# 02_Solenoid_Driver.net
KiCad netlist of a schematic drawn in Altium Designer
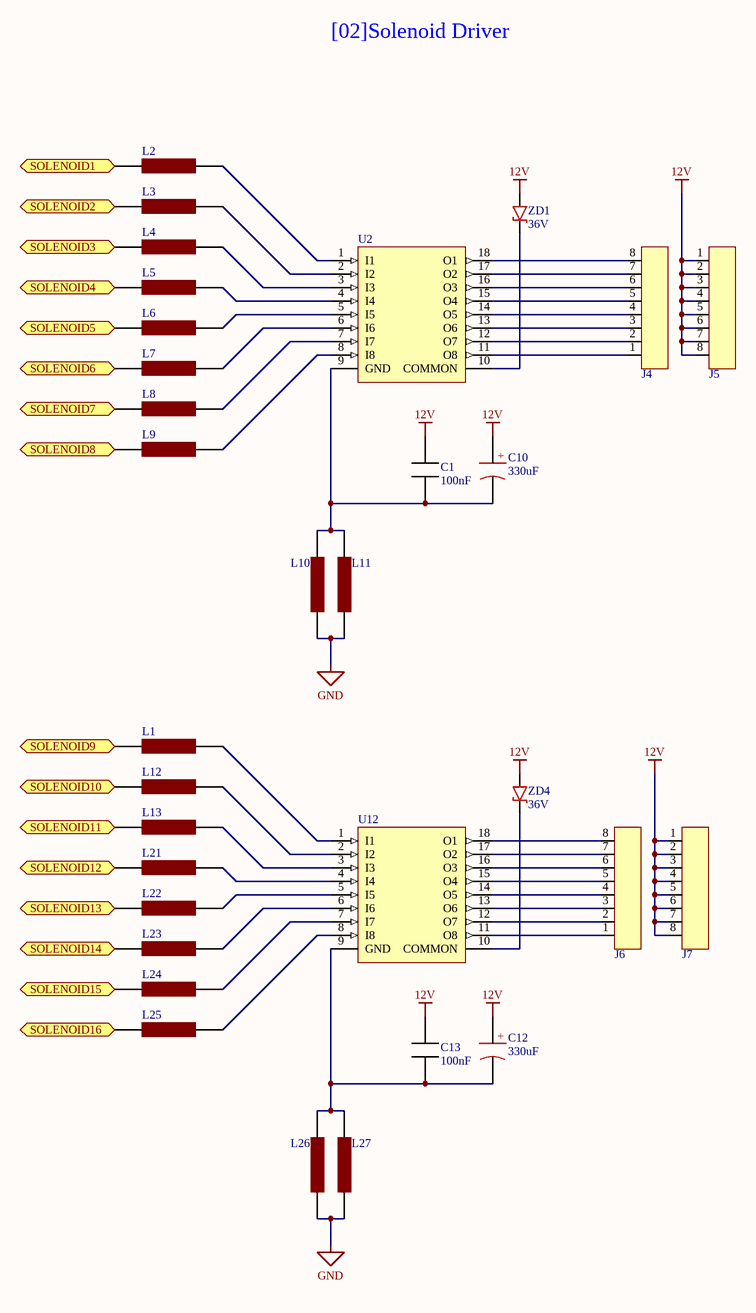
[diagram p0: [02]Solenoid Driver.SchDoc]

(export (version "E")
  (design (tool "Eeschema 10.0.6"))
  (components
    (comp (ref "C1")
      (value "100nF")
      (footprint "CAPC2012X09N")
      (description "CAP CER 0.1UF 50V Y5V 0805")
      (fields
        (field (name "MANUFACTURER") "Samsung Electro-Mechanics America, Inc.")
        (field (name "MANUFACTURER PART NUMBER") "CL21F104ZBCNNNC")
      )
      (libsource (lib "AMMDK Parts") (part "CL21F104ZBCNNNC"))
    )
    (comp (ref "C10")
      (value "330uF")
      (footprint "CAPAE137130X140M")
      (description "CAP ALUM 330UF 20% 35V SMD")
      (libsource (lib "AMMDK Parts") (part "EMVH350ARA331MKE0S"))
    )
    (comp (ref "C12")
      (value "330uF")
      (footprint "CAPAE137130X140M")
      (description "CAP ALUM 330UF 20% 35V SMD")
      (libsource (lib "AMMDK Parts") (part "EMVH350ARA331MKE0S"))
    )
    (comp (ref "C13")
      (value "100nF")
      (footprint "CAPC2012X09N")
      (description "CAP CER 0.1UF 50V Y5V 0805")
      (fields
        (field (name "MANUFACTURER") "Samsung Electro-Mechanics America, Inc.")
        (field (name "MANUFACTURER PART NUMBER") "CL21F104ZBCNNNC")
      )
      (libsource (lib "AMMDK Parts") (part "CL21F104ZBCNNNC"))
    )
    (comp (ref "J4")
      (value "1771156")
      (footprint "1771156")
      (description "CONN TERM BLK 8POS 2.5MM SMD")
      (fields (field (name "MANUFACTURER") "Phoenix Contact"))
      (libsource (lib "") (part "1771156_1"))
    )
    (comp (ref "J5")
      (value "1771156")
      (footprint "1771156")
      (description "CONN TERM BLK 8POS 2.5MM SMD")
      (fields (field (name "MANUFACTURER") "Phoenix Contact"))
      (libsource (lib "AMMDK Parts") (part "1771156"))
    )
    (comp (ref "J6")
      (value "1771156")
      (footprint "1771156")
      (description "CONN TERM BLK 8POS 2.5MM SMD")
      (fields (field (name "MANUFACTURER") "Phoenix Contact"))
      (libsource (lib "") (part "1771156_1"))
    )
    (comp (ref "J7")
      (value "1771156")
      (footprint "1771156")
      (description "CONN TERM BLK 8POS 2.5MM SMD")
      (fields (field (name "MANUFACTURER") "Phoenix Contact"))
      (libsource (lib "AMMDK Parts") (part "1771156"))
    )
    (comp (ref "L1")
      (value "MH2029-300Y")
      (footprint "INDC2012X11N")
      (description "EMI Filter Beads, Chips & Arrays Impedance 30ohms IDC 3.0")
      (fields (field (name "MANUFACTURER") "Bourns") (field (name "TOLERANCE") "25 %"))
      (libsource (lib "AMMDK Parts") (part "MH2029-300Y"))
    )
    (comp (ref "L2")
      (value "MH2029-300Y")
      (footprint "INDC2012X11N")
      (description "EMI Filter Beads, Chips & Arrays Impedance 30ohms IDC 3.0")
      (fields (field (name "MANUFACTURER") "Bourns") (field (name "TOLERANCE") "25 %"))
      (libsource (lib "AMMDK Parts") (part "MH2029-300Y"))
    )
    (comp (ref "L3")
      (value "MH2029-300Y")
      (footprint "INDC2012X11N")
      (description "EMI Filter Beads, Chips & Arrays Impedance 30ohms IDC 3.0")
      (fields (field (name "MANUFACTURER") "Bourns") (field (name "TOLERANCE") "25 %"))
      (libsource (lib "AMMDK Parts") (part "MH2029-300Y"))
    )
    (comp (ref "L4")
      (value "MH2029-300Y")
      (footprint "INDC2012X11N")
      (description "EMI Filter Beads, Chips & Arrays Impedance 30ohms IDC 3.0")
      (fields (field (name "MANUFACTURER") "Bourns") (field (name "TOLERANCE") "25 %"))
      (libsource (lib "AMMDK Parts") (part "MH2029-300Y"))
    )
    (comp (ref "L5")
      (value "MH2029-300Y")
      (footprint "INDC2012X11N")
      (description "EMI Filter Beads, Chips & Arrays Impedance 30ohms IDC 3.0")
      (fields (field (name "MANUFACTURER") "Bourns") (field (name "TOLERANCE") "25 %"))
      (libsource (lib "AMMDK Parts") (part "MH2029-300Y"))
    )
    (comp (ref "L6")
      (value "MH2029-300Y")
      (footprint "INDC2012X11N")
      (description "EMI Filter Beads, Chips & Arrays Impedance 30ohms IDC 3.0")
      (fields (field (name "MANUFACTURER") "Bourns") (field (name "TOLERANCE") "25 %"))
      (libsource (lib "AMMDK Parts") (part "MH2029-300Y"))
    )
    (comp (ref "L7")
      (value "MH2029-300Y")
      (footprint "INDC2012X11N")
      (description "EMI Filter Beads, Chips & Arrays Impedance 30ohms IDC 3.0")
      (fields (field (name "MANUFACTURER") "Bourns") (field (name "TOLERANCE") "25 %"))
      (libsource (lib "AMMDK Parts") (part "MH2029-300Y"))
    )
    (comp (ref "L8")
      (value "MH2029-300Y")
      (footprint "INDC2012X11N")
      (description "EMI Filter Beads, Chips & Arrays Impedance 30ohms IDC 3.0")
      (fields (field (name "MANUFACTURER") "Bourns") (field (name "TOLERANCE") "25 %"))
      (libsource (lib "AMMDK Parts") (part "MH2029-300Y"))
    )
    (comp (ref "L9")
      (value "MH2029-300Y")
      (footprint "INDC2012X11N")
      (description "EMI Filter Beads, Chips & Arrays Impedance 30ohms IDC 3.0")
      (fields (field (name "MANUFACTURER") "Bourns") (field (name "TOLERANCE") "25 %"))
      (libsource (lib "AMMDK Parts") (part "MH2029-300Y"))
    )
    (comp (ref "L10")
      (value "MH2029-300Y")
      (footprint "INDC2012X11N")
      (description "EMI Filter Beads, Chips & Arrays Impedance 30ohms IDC 3.0")
      (fields (field (name "MANUFACTURER") "Bourns") (field (name "TOLERANCE") "25 %"))
      (libsource (lib "") (part "MH2029-300Y_1"))
    )
    (comp (ref "L11")
      (value "MH2029-300Y")
      (footprint "INDC2012X11N")
      (description "EMI Filter Beads, Chips & Arrays Impedance 30ohms IDC 3.0")
      (fields (field (name "MANUFACTURER") "Bourns") (field (name "TOLERANCE") "25 %"))
      (libsource (lib "") (part "MH2029-300Y_1"))
    )
    (comp (ref "L12")
      (value "MH2029-300Y")
      (footprint "INDC2012X11N")
      (description "EMI Filter Beads, Chips & Arrays Impedance 30ohms IDC 3.0")
      (fields (field (name "MANUFACTURER") "Bourns") (field (name "TOLERANCE") "25 %"))
      (libsource (lib "AMMDK Parts") (part "MH2029-300Y"))
    )
    (comp (ref "L13")
      (value "MH2029-300Y")
      (footprint "INDC2012X11N")
      (description "EMI Filter Beads, Chips & Arrays Impedance 30ohms IDC 3.0")
      (fields (field (name "MANUFACTURER") "Bourns") (field (name "TOLERANCE") "25 %"))
      (libsource (lib "AMMDK Parts") (part "MH2029-300Y"))
    )
    (comp (ref "L21")
      (value "MH2029-300Y")
      (footprint "INDC2012X11N")
      (description "EMI Filter Beads, Chips & Arrays Impedance 30ohms IDC 3.0")
      (fields (field (name "MANUFACTURER") "Bourns") (field (name "TOLERANCE") "25 %"))
      (libsource (lib "AMMDK Parts") (part "MH2029-300Y"))
    )
    (comp (ref "L22")
      (value "MH2029-300Y")
      (footprint "INDC2012X11N")
      (description "EMI Filter Beads, Chips & Arrays Impedance 30ohms IDC 3.0")
      (fields (field (name "MANUFACTURER") "Bourns") (field (name "TOLERANCE") "25 %"))
      (libsource (lib "AMMDK Parts") (part "MH2029-300Y"))
    )
    (comp (ref "L23")
      (value "MH2029-300Y")
      (footprint "INDC2012X11N")
      (description "EMI Filter Beads, Chips & Arrays Impedance 30ohms IDC 3.0")
      (fields (field (name "MANUFACTURER") "Bourns") (field (name "TOLERANCE") "25 %"))
      (libsource (lib "AMMDK Parts") (part "MH2029-300Y"))
    )
    (comp (ref "L24")
      (value "MH2029-300Y")
      (footprint "INDC2012X11N")
      (description "EMI Filter Beads, Chips & Arrays Impedance 30ohms IDC 3.0")
      (fields (field (name "MANUFACTURER") "Bourns") (field (name "TOLERANCE") "25 %"))
      (libsource (lib "AMMDK Parts") (part "MH2029-300Y"))
    )
    (comp (ref "L25")
      (value "MH2029-300Y")
      (footprint "INDC2012X11N")
      (description "EMI Filter Beads, Chips & Arrays Impedance 30ohms IDC 3.0")
      (fields (field (name "MANUFACTURER") "Bourns") (field (name "TOLERANCE") "25 %"))
      (libsource (lib "AMMDK Parts") (part "MH2029-300Y"))
    )
    (comp (ref "L26")
      (value "MH2029-300Y")
      (footprint "INDC2012X11N")
      (description "EMI Filter Beads, Chips & Arrays Impedance 30ohms IDC 3.0")
      (fields (field (name "MANUFACTURER") "Bourns") (field (name "TOLERANCE") "25 %"))
      (libsource (lib "") (part "MH2029-300Y_1"))
    )
    (comp (ref "L27")
      (value "MH2029-300Y")
      (footprint "INDC2012X11N")
      (description "EMI Filter Beads, Chips & Arrays Impedance 30ohms IDC 3.0")
      (fields (field (name "MANUFACTURER") "Bourns") (field (name "TOLERANCE") "25 %"))
      (libsource (lib "") (part "MH2029-300Y_1"))
    )
    (comp (ref "U2")
      (value "TBD62083A")
      (footprint "TSOP65P640X155-18N")
      (description "8channel source type DMOS transistor array")
      (libsource (lib "AMMDK Parts") (part "TBD62083A"))
    )
    (comp (ref "U12")
      (value "TBD62083A")
      (footprint "TSOP65P640X155-18N")
      (description "8channel source type DMOS transistor array")
      (libsource (lib "AMMDK Parts") (part "TBD62083A"))
    )
    (comp (ref "ZD1")
      (value "36V")
      (footprint "SOT95P237X111-3N")
      (description "Zener Diode 36V 225mW ±6%")
      (libsource (lib "AMMDK Parts") (part "BZX84C36LT1G"))
    )
    (comp (ref "ZD4")
      (value "36V")
      (footprint "SOT95P237X111-3N")
      (description "Zener Diode 36V 225mW ±6%")
      (libsource (lib "AMMDK Parts") (part "BZX84C36LT1G"))
    )
  )
  (nets
    (net (code "1") (name "/SOLENOID1") (class "Default")
      (node (ref "L2") (pin "1") (pinfunction "1_1") (pintype "passive"))
    )
    (net (code "2") (name "/SOLENOID2") (class "Default")
      (node (ref "L3") (pin "1") (pinfunction "1_1") (pintype "passive"))
    )
    (net (code "3") (name "/SOLENOID3") (class "Default")
      (node (ref "L4") (pin "1") (pinfunction "1_1") (pintype "passive"))
    )
    (net (code "4") (name "/SOLENOID4") (class "Default")
      (node (ref "L5") (pin "1") (pinfunction "1_1") (pintype "passive"))
    )
    (net (code "5") (name "/SOLENOID5") (class "Default")
      (node (ref "L6") (pin "1") (pinfunction "1_1") (pintype "passive"))
    )
    (net (code "6") (name "/SOLENOID6") (class "Default")
      (node (ref "L7") (pin "1") (pinfunction "1_1") (pintype "passive"))
    )
    (net (code "7") (name "/SOLENOID7") (class "Default")
      (node (ref "L8") (pin "1") (pinfunction "1_1") (pintype "passive"))
    )
    (net (code "8") (name "/SOLENOID8") (class "Default")
      (node (ref "L9") (pin "1") (pinfunction "1_1") (pintype "passive"))
    )
    (net (code "9") (name "/SOLENOID9") (class "Default")
      (node (ref "L1") (pin "1") (pinfunction "1_1") (pintype "passive"))
    )
    (net (code "10") (name "/SOLENOID10") (class "Default")
      (node (ref "L12") (pin "1") (pinfunction "1_1") (pintype "passive"))
    )
    (net (code "11") (name "/SOLENOID11") (class "Default")
      (node (ref "L13") (pin "1") (pinfunction "1_1") (pintype "passive"))
    )
    (net (code "12") (name "/SOLENOID12") (class "Default")
      (node (ref "L21") (pin "1") (pinfunction "1_1") (pintype "passive"))
    )
    (net (code "13") (name "/SOLENOID13") (class "Default")
      (node (ref "L22") (pin "1") (pinfunction "1_1") (pintype "passive"))
    )
    (net (code "14") (name "/SOLENOID14") (class "Default")
      (node (ref "L23") (pin "1") (pinfunction "1_1") (pintype "passive"))
    )
    (net (code "15") (name "/SOLENOID15") (class "Default")
      (node (ref "L24") (pin "1") (pinfunction "1_1") (pintype "passive"))
    )
    (net (code "16") (name "/SOLENOID16") (class "Default")
      (node (ref "L25") (pin "1") (pinfunction "1_1") (pintype "passive"))
    )
    (net (code "17") (name "12V") (class "Default")
      (node (ref "C1") (pin "2") (pinfunction "2_2") (pintype "passive"))
      (node (ref "C10") (pin "1") (pinfunction "1_1") (pintype "passive"))
      (node (ref "C12") (pin "1") (pinfunction "1_1") (pintype "passive"))
      (node (ref "C13") (pin "2") (pinfunction "2_2") (pintype "passive"))
      (node (ref "J5") (pin "1") (pinfunction "1_1") (pintype "passive"))
      (node (ref "J5") (pin "2") (pinfunction "2_2") (pintype "passive"))
      (node (ref "J5") (pin "3") (pinfunction "3_3") (pintype "passive"))
      (node (ref "J5") (pin "4") (pinfunction "4_4") (pintype "passive"))
      (node (ref "J5") (pin "5") (pinfunction "5_5") (pintype "passive"))
      (node (ref "J5") (pin "6") (pinfunction "6_6") (pintype "passive"))
      (node (ref "J5") (pin "7") (pinfunction "7_7") (pintype "passive"))
      (node (ref "J5") (pin "8") (pinfunction "8_8") (pintype "passive"))
      (node (ref "J7") (pin "1") (pinfunction "1_1") (pintype "passive"))
      (node (ref "J7") (pin "2") (pinfunction "2_2") (pintype "passive"))
      (node (ref "J7") (pin "3") (pinfunction "3_3") (pintype "passive"))
      (node (ref "J7") (pin "4") (pinfunction "4_4") (pintype "passive"))
      (node (ref "J7") (pin "5") (pinfunction "5_5") (pintype "passive"))
      (node (ref "J7") (pin "6") (pinfunction "6_6") (pintype "passive"))
      (node (ref "J7") (pin "7") (pinfunction "7_7") (pintype "passive"))
      (node (ref "J7") (pin "8") (pinfunction "8_8") (pintype "passive"))
      (node (ref "ZD1") (pin "A") (pinfunction "A_A") (pintype "passive"))
      (node (ref "ZD4") (pin "A") (pinfunction "A_A") (pintype "passive"))
    )
    (net (code "18") (name "GND") (class "Default")
      (node (ref "L10") (pin "1") (pinfunction "1_1") (pintype "passive"))
      (node (ref "L11") (pin "1") (pinfunction "1_1") (pintype "passive"))
      (node (ref "L26") (pin "1") (pinfunction "1_1") (pintype "passive"))
      (node (ref "L27") (pin "1") (pinfunction "1_1") (pintype "passive"))
    )
    (net (code "19") (name "Net-(U2-COMMON)") (class "Default")
      (node (ref "U2") (pin "10") (pinfunction "COMMON_10") (pintype "power_in"))
      (node (ref "ZD1") (pin "K") (pinfunction "K_K") (pintype "passive"))
    )
    (net (code "20") (name "Net-(U2-GND)") (class "Default")
      (node (ref "C1") (pin "1") (pinfunction "1_1") (pintype "passive"))
      (node (ref "C10") (pin "2") (pinfunction "2_2") (pintype "passive"))
      (node (ref "L10") (pin "2") (pinfunction "2_2") (pintype "passive"))
      (node (ref "L11") (pin "2") (pinfunction "2_2") (pintype "passive"))
      (node (ref "U2") (pin "9") (pinfunction "GND_9") (pintype "power_in"))
    )
    (net (code "21") (name "Net-(U2-I1)") (class "Default")
      (node (ref "L2") (pin "2") (pinfunction "2_2") (pintype "passive"))
      (node (ref "U2") (pin "1") (pinfunction "I1_1") (pintype "input"))
    )
    (net (code "22") (name "Net-(U2-I2)") (class "Default")
      (node (ref "L3") (pin "2") (pinfunction "2_2") (pintype "passive"))
      (node (ref "U2") (pin "2") (pinfunction "I2_2") (pintype "input"))
    )
    (net (code "23") (name "Net-(U2-I3)") (class "Default")
      (node (ref "L4") (pin "2") (pinfunction "2_2") (pintype "passive"))
      (node (ref "U2") (pin "3") (pinfunction "I3_3") (pintype "input"))
    )
    (net (code "24") (name "Net-(U2-I4)") (class "Default")
      (node (ref "L5") (pin "2") (pinfunction "2_2") (pintype "passive"))
      (node (ref "U2") (pin "4") (pinfunction "I4_4") (pintype "input"))
    )
    (net (code "25") (name "Net-(U2-I5)") (class "Default")
      (node (ref "L6") (pin "2") (pinfunction "2_2") (pintype "passive"))
      (node (ref "U2") (pin "5") (pinfunction "I5_5") (pintype "input"))
    )
    (net (code "26") (name "Net-(U2-I6)") (class "Default")
      (node (ref "L7") (pin "2") (pinfunction "2_2") (pintype "passive"))
      (node (ref "U2") (pin "6") (pinfunction "I6_6") (pintype "input"))
    )
    (net (code "27") (name "Net-(U2-I7)") (class "Default")
      (node (ref "L8") (pin "2") (pinfunction "2_2") (pintype "passive"))
      (node (ref "U2") (pin "7") (pinfunction "I7_7") (pintype "input"))
    )
    (net (code "28") (name "Net-(U2-I8)") (class "Default")
      (node (ref "L9") (pin "2") (pinfunction "2_2") (pintype "passive"))
      (node (ref "U2") (pin "8") (pinfunction "I8_8") (pintype "input"))
    )
    (net (code "29") (name "Net-(U2-O1)") (class "Default")
      (node (ref "J4") (pin "8") (pinfunction "8_8") (pintype "passive"))
      (node (ref "U2") (pin "18") (pinfunction "O1_18") (pintype "output"))
    )
    (net (code "30") (name "Net-(U2-O2)") (class "Default")
      (node (ref "J4") (pin "7") (pinfunction "7_7") (pintype "passive"))
      (node (ref "U2") (pin "17") (pinfunction "O2_17") (pintype "output"))
    )
    (net (code "31") (name "Net-(U2-O3)") (class "Default")
      (node (ref "J4") (pin "6") (pinfunction "6_6") (pintype "passive"))
      (node (ref "U2") (pin "16") (pinfunction "O3_16") (pintype "output"))
    )
    (net (code "32") (name "Net-(U2-O4)") (class "Default")
      (node (ref "J4") (pin "5") (pinfunction "5_5") (pintype "passive"))
      (node (ref "U2") (pin "15") (pinfunction "O4_15") (pintype "output"))
    )
    (net (code "33") (name "Net-(U2-O5)") (class "Default")
      (node (ref "J4") (pin "4") (pinfunction "4_4") (pintype "passive"))
      (node (ref "U2") (pin "14") (pinfunction "O5_14") (pintype "output"))
    )
    (net (code "34") (name "Net-(U2-O6)") (class "Default")
      (node (ref "J4") (pin "3") (pinfunction "3_3") (pintype "passive"))
      (node (ref "U2") (pin "13") (pinfunction "O6_13") (pintype "output"))
    )
    (net (code "35") (name "Net-(U2-O7)") (class "Default")
      (node (ref "J4") (pin "2") (pinfunction "2_2") (pintype "passive"))
      (node (ref "U2") (pin "12") (pinfunction "O7_12") (pintype "output"))
    )
    (net (code "36") (name "Net-(U2-O8)") (class "Default")
      (node (ref "J4") (pin "1") (pinfunction "1_1") (pintype "passive"))
      (node (ref "U2") (pin "11") (pinfunction "O8_11") (pintype "output"))
    )
    (net (code "37") (name "Net-(U12-COMMON)") (class "Default")
      (node (ref "U12") (pin "10") (pinfunction "COMMON_10") (pintype "power_in"))
      (node (ref "ZD4") (pin "K") (pinfunction "K_K") (pintype "passive"))
    )
    (net (code "38") (name "Net-(U12-GND)") (class "Default")
      (node (ref "C12") (pin "2") (pinfunction "2_2") (pintype "passive"))
      (node (ref "C13") (pin "1") (pinfunction "1_1") (pintype "passive"))
      (node (ref "L26") (pin "2") (pinfunction "2_2") (pintype "passive"))
      (node (ref "L27") (pin "2") (pinfunction "2_2") (pintype "passive"))
      (node (ref "U12") (pin "9") (pinfunction "GND_9") (pintype "power_in"))
    )
    (net (code "39") (name "Net-(U12-I1)") (class "Default")
      (node (ref "L1") (pin "2") (pinfunction "2_2") (pintype "passive"))
      (node (ref "U12") (pin "1") (pinfunction "I1_1") (pintype "input"))
    )
    (net (code "40") (name "Net-(U12-I2)") (class "Default")
      (node (ref "L12") (pin "2") (pinfunction "2_2") (pintype "passive"))
      (node (ref "U12") (pin "2") (pinfunction "I2_2") (pintype "input"))
    )
    (net (code "41") (name "Net-(U12-I3)") (class "Default")
      (node (ref "L13") (pin "2") (pinfunction "2_2") (pintype "passive"))
      (node (ref "U12") (pin "3") (pinfunction "I3_3") (pintype "input"))
    )
    (net (code "42") (name "Net-(U12-I4)") (class "Default")
      (node (ref "L21") (pin "2") (pinfunction "2_2") (pintype "passive"))
      (node (ref "U12") (pin "4") (pinfunction "I4_4") (pintype "input"))
    )
    (net (code "43") (name "Net-(U12-I5)") (class "Default")
      (node (ref "L22") (pin "2") (pinfunction "2_2") (pintype "passive"))
      (node (ref "U12") (pin "5") (pinfunction "I5_5") (pintype "input"))
    )
    (net (code "44") (name "Net-(U12-I6)") (class "Default")
      (node (ref "L23") (pin "2") (pinfunction "2_2") (pintype "passive"))
      (node (ref "U12") (pin "6") (pinfunction "I6_6") (pintype "input"))
    )
    (net (code "45") (name "Net-(U12-I7)") (class "Default")
      (node (ref "L24") (pin "2") (pinfunction "2_2") (pintype "passive"))
      (node (ref "U12") (pin "7") (pinfunction "I7_7") (pintype "input"))
    )
    (net (code "46") (name "Net-(U12-I8)") (class "Default")
      (node (ref "L25") (pin "2") (pinfunction "2_2") (pintype "passive"))
      (node (ref "U12") (pin "8") (pinfunction "I8_8") (pintype "input"))
    )
    (net (code "47") (name "Net-(U12-O1)") (class "Default")
      (node (ref "J6") (pin "8") (pinfunction "8_8") (pintype "passive"))
      (node (ref "U12") (pin "18") (pinfunction "O1_18") (pintype "output"))
    )
    (net (code "48") (name "Net-(U12-O2)") (class "Default")
      (node (ref "J6") (pin "7") (pinfunction "7_7") (pintype "passive"))
      (node (ref "U12") (pin "17") (pinfunction "O2_17") (pintype "output"))
    )
    (net (code "49") (name "Net-(U12-O3)") (class "Default")
      (node (ref "J6") (pin "6") (pinfunction "6_6") (pintype "passive"))
      (node (ref "U12") (pin "16") (pinfunction "O3_16") (pintype "output"))
    )
    (net (code "50") (name "Net-(U12-O4)") (class "Default")
      (node (ref "J6") (pin "5") (pinfunction "5_5") (pintype "passive"))
      (node (ref "U12") (pin "15") (pinfunction "O4_15") (pintype "output"))
    )
    (net (code "51") (name "Net-(U12-O5)") (class "Default")
      (node (ref "J6") (pin "4") (pinfunction "4_4") (pintype "passive"))
      (node (ref "U12") (pin "14") (pinfunction "O5_14") (pintype "output"))
    )
    (net (code "52") (name "Net-(U12-O6)") (class "Default")
      (node (ref "J6") (pin "3") (pinfunction "3_3") (pintype "passive"))
      (node (ref "U12") (pin "13") (pinfunction "O6_13") (pintype "output"))
    )
    (net (code "53") (name "Net-(U12-O7)") (class "Default")
      (node (ref "J6") (pin "2") (pinfunction "2_2") (pintype "passive"))
      (node (ref "U12") (pin "12") (pinfunction "O7_12") (pintype "output"))
    )
    (net (code "54") (name "Net-(U12-O8)") (class "Default")
      (node (ref "J6") (pin "1") (pinfunction "1_1") (pintype "passive"))
      (node (ref "U12") (pin "11") (pinfunction "O8_11") (pintype "output"))
    )
  )
)
